# Mergen_Ground_Station_V2_0.net
KiCad netlist of a schematic drawn in EAGLE
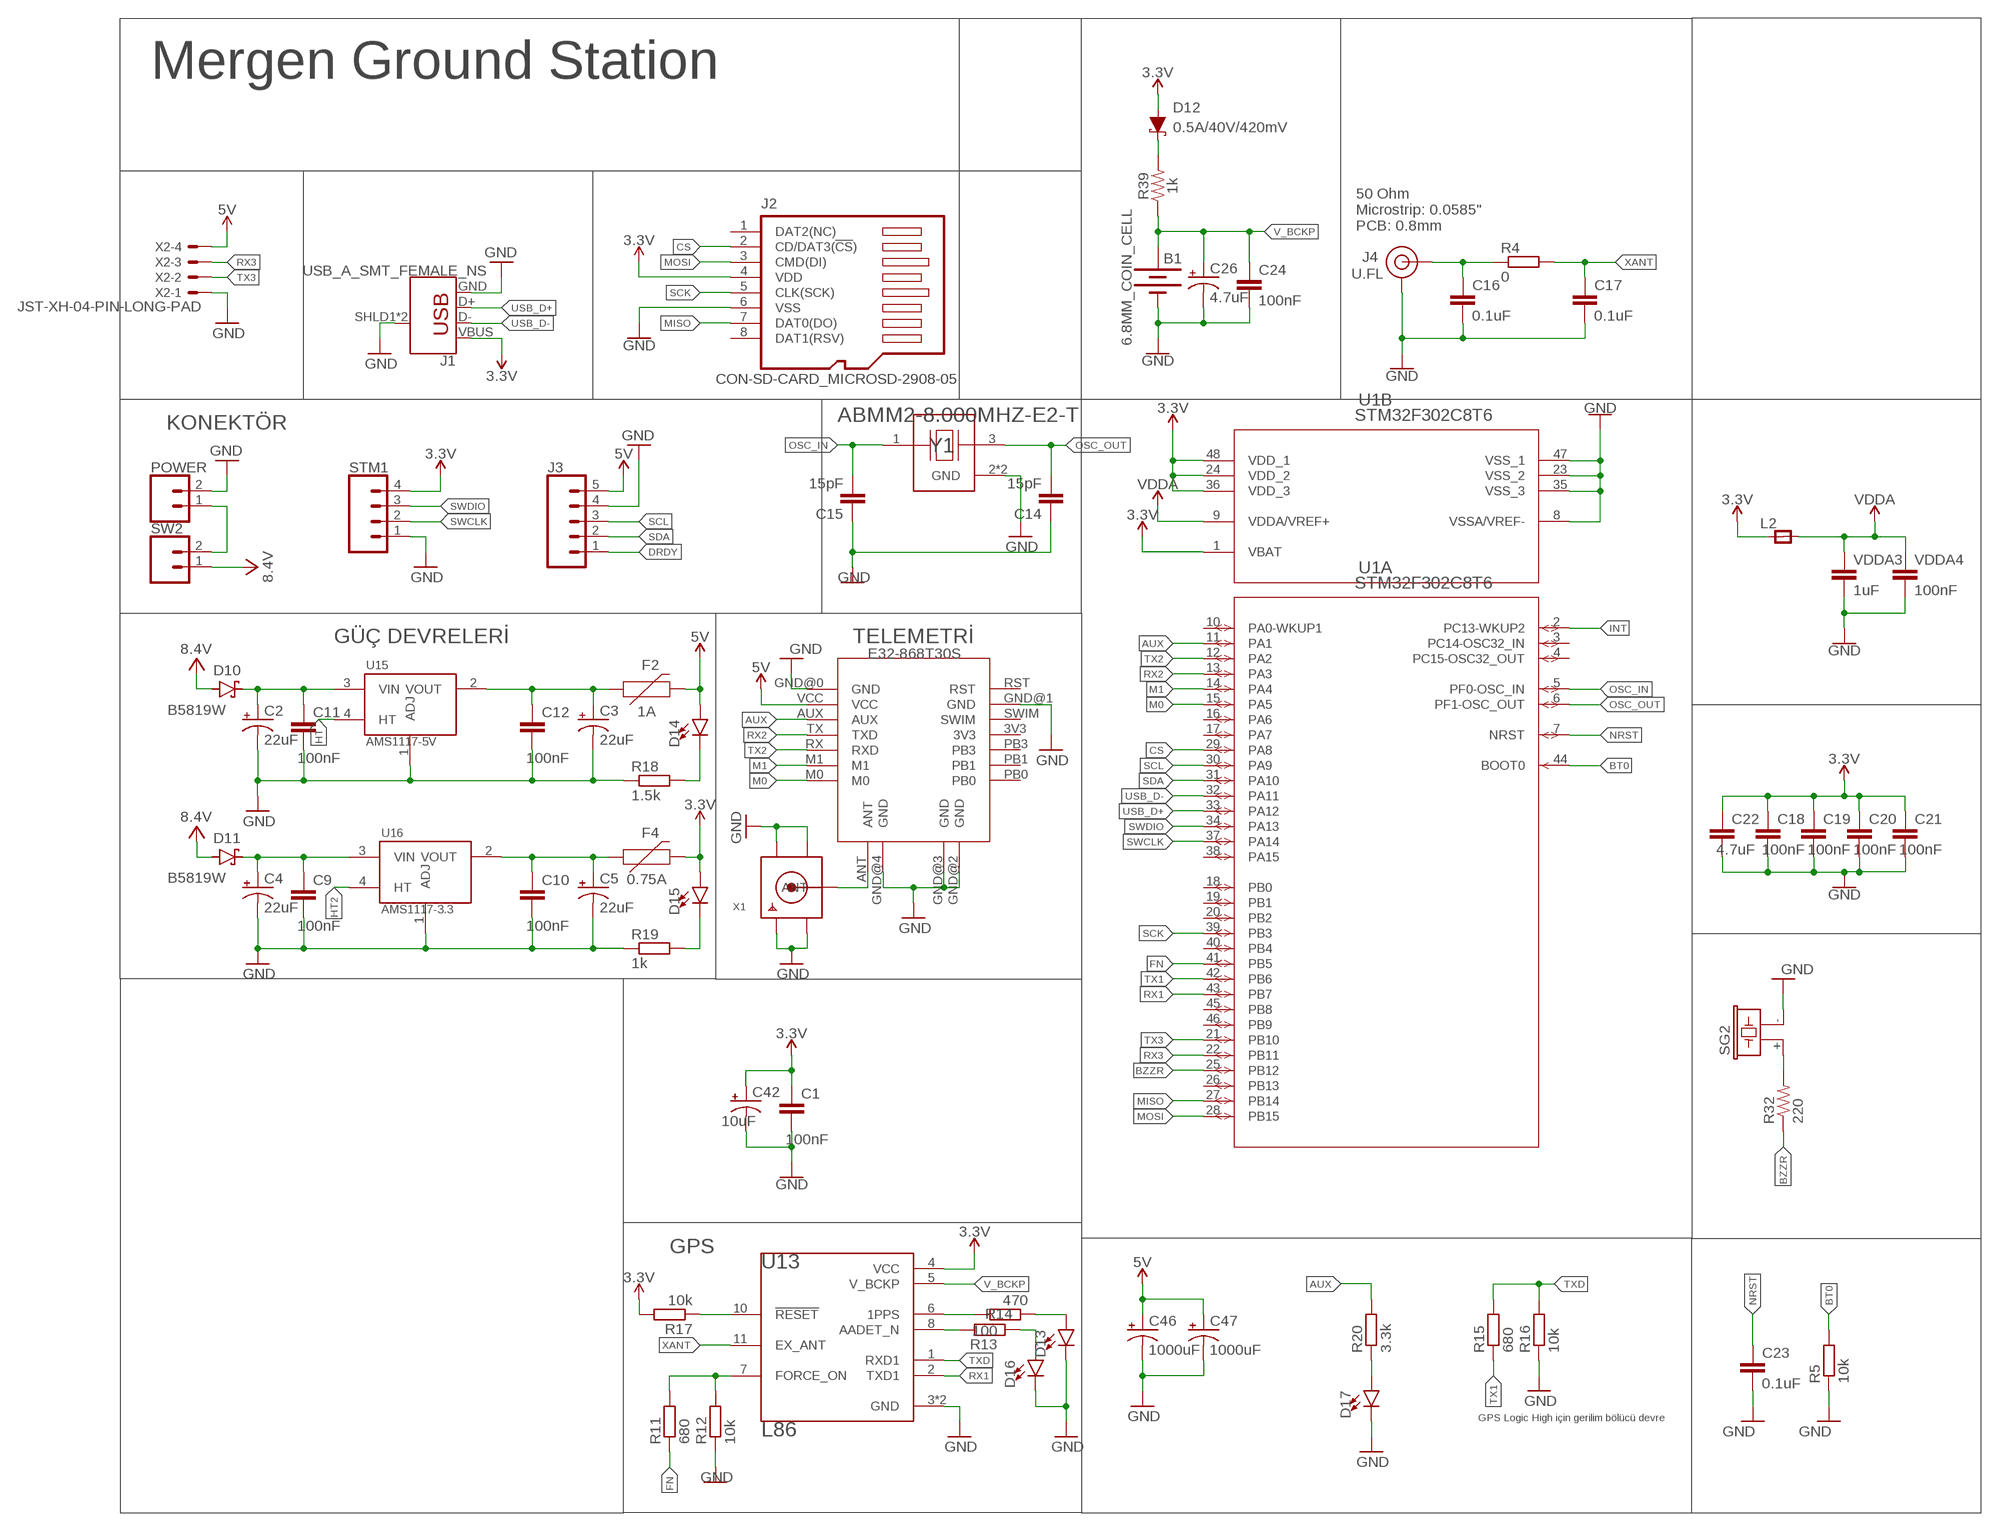
[diagram p0: schematic, sheet 1]

(export (version "E")
  (design (tool "Eeschema 10.0.6"))
  (components
    (comp (ref "B1")
      (value "6.8MM_COIN_CELL")
      (footprint "eagle-import:BATTCON-6.8MM")
      (libsource (lib "eagle-import") (part "BATTERY-6.8MM_SMD"))
    )
    (comp (ref "C1")
      (value "100nF")
      (footprint "eagle-import:C0603")
      (libsource (lib "eagle-import") (part "C-EUC0603"))
    )
    (comp (ref "C2")
      (value "22uF")
      (footprint "eagle-import:CT3528")
      (libsource (lib "eagle-import") (part "rcl_334_CPOL-USCT3528"))
    )
    (comp (ref "C3")
      (value "22uF")
      (footprint "eagle-import:CT3528")
      (libsource (lib "eagle-import") (part "rcl_334_CPOL-USCT3528"))
    )
    (comp (ref "C4")
      (value "22uF")
      (footprint "eagle-import:CT3528")
      (libsource (lib "eagle-import") (part "rcl_334_CPOL-USCT3528"))
    )
    (comp (ref "C5")
      (value "22uF")
      (footprint "eagle-import:CT3528")
      (libsource (lib "eagle-import") (part "rcl_334_CPOL-USCT3528"))
    )
    (comp (ref "C9")
      (value "100nF")
      (footprint "eagle-import:C0603")
      (libsource (lib "eagle-import") (part "C-EUC0603"))
    )
    (comp (ref "C10")
      (value "100nF")
      (footprint "eagle-import:C0603")
      (libsource (lib "eagle-import") (part "C-EUC0603"))
    )
    (comp (ref "C11")
      (value "100nF")
      (footprint "eagle-import:C0603")
      (libsource (lib "eagle-import") (part "C-EUC0603"))
    )
    (comp (ref "C12")
      (value "100nF")
      (footprint "eagle-import:C0603")
      (libsource (lib "eagle-import") (part "C-EUC0603"))
    )
    (comp (ref "C14")
      (value "15pF")
      (footprint "eagle-import:C0603")
      (libsource (lib "eagle-import") (part "C-EUC0603"))
    )
    (comp (ref "C15")
      (value "15pF")
      (footprint "eagle-import:C0603")
      (libsource (lib "eagle-import") (part "C-EUC0603"))
    )
    (comp (ref "C16")
      (value "0.1uF")
      (footprint "eagle-import:C0603")
      (libsource (lib "eagle-import") (part "C-EUC0603"))
    )
    (comp (ref "C17")
      (value "0.1uF")
      (footprint "eagle-import:C0603")
      (libsource (lib "eagle-import") (part "C-EUC0603"))
    )
    (comp (ref "C18")
      (value "100nF")
      (footprint "eagle-import:C0603")
      (libsource (lib "eagle-import") (part "C-EUC0603"))
    )
    (comp (ref "C19")
      (value "100nF")
      (footprint "eagle-import:C0603")
      (libsource (lib "eagle-import") (part "C-EUC0603"))
    )
    (comp (ref "C20")
      (value "100nF")
      (footprint "eagle-import:C0603")
      (libsource (lib "eagle-import") (part "C-EUC0603"))
    )
    (comp (ref "C21")
      (value "100nF")
      (footprint "eagle-import:C0603")
      (libsource (lib "eagle-import") (part "C-EUC0603"))
    )
    (comp (ref "C22")
      (value "4.7uF")
      (footprint "eagle-import:C0603")
      (libsource (lib "eagle-import") (part "C-EUC0603"))
    )
    (comp (ref "C23")
      (value "0.1uF")
      (footprint "eagle-import:C0603")
      (libsource (lib "eagle-import") (part "C-EUC0603"))
    )
    (comp (ref "C24")
      (value "100nF")
      (footprint "eagle-import:C0603")
      (libsource (lib "eagle-import") (part "C-EUC0603"))
    )
    (comp (ref "C26")
      (value "4.7uF")
      (footprint "eagle-import:A_3216-18R")
      (libsource (lib "eagle-import") (part "rcl_334_CPOL-USA/3216-18R"))
    )
    (comp (ref "C42")
      (value "10uF")
      (footprint "eagle-import:EIA3216")
      (libsource (lib "eagle-import") (part "10UF-POLAR-EIA3216-16V-10%(TANT)"))
    )
    (comp (ref "C46")
      (value "1000uF")
      (footprint "eagle-import:150CLZ-1010")
      (libsource (lib "eagle-import") (part "CPOL-US150CLZ-1010"))
    )
    (comp (ref "C47")
      (value "1000uF")
      (footprint "eagle-import:150CLZ-1010")
      (libsource (lib "eagle-import") (part "CPOL-US150CLZ-1010"))
    )
    (comp (ref "D10")
      (value "B5819W")
      (footprint "eagle-import:SODFL3718X115")
      (fields (field (name "MANUFACTURER") "ON Semiconductor") (field (name "MPN") "MBR0520LT1G"))
      (libsource (lib "eagle-import") (part "SCHOTTKY_DO-219MBR0520LT1G"))
    )
    (comp (ref "D11")
      (value "B5819W")
      (footprint "eagle-import:SODFL3718X115")
      (fields (field (name "MANUFACTURER") "ON Semiconductor") (field (name "MPN") "MBR0520LT1G"))
      (libsource (lib "eagle-import") (part "SCHOTTKY_DO-219MBR0520LT1G"))
    )
    (comp (ref "D12")
      (value "0.5A/40V/420mV")
      (footprint "eagle-import:SOD-323")
      (libsource (lib "eagle-import") (part "DIODE-SCHOTTKY-PMEG4005EJ"))
    )
    (comp (ref "D13")
      (value "LED0603")
      (footprint "eagle-import:LED-0603")
      (libsource (lib "eagle-import") (part "LED0603"))
    )
    (comp (ref "D14")
      (value "LED0603")
      (footprint "eagle-import:LED-0603")
      (libsource (lib "eagle-import") (part "LED0603"))
    )
    (comp (ref "D15")
      (value "LED0603")
      (footprint "eagle-import:LED-0603")
      (libsource (lib "eagle-import") (part "LED0603"))
    )
    (comp (ref "D16")
      (value "LED0603")
      (footprint "eagle-import:LED-0603")
      (libsource (lib "eagle-import") (part "LED0603"))
    )
    (comp (ref "D17")
      (value "LED0603")
      (footprint "eagle-import:LED-0603")
      (libsource (lib "eagle-import") (part "LED0603"))
    )
    (comp (ref "F2")
      (value "1A")
      (footprint "eagle-import:1206")
      (libsource (lib "eagle-import") (part "PPTC_HALF-AMP"))
    )
    (comp (ref "F4")
      (value "0.75A")
      (footprint "eagle-import:1206")
      (libsource (lib "eagle-import") (part "PPTC_HALF-AMP"))
    )
    (comp (ref "J1")
      (value "USB_A_SMT_FEMALE_NS")
      (footprint "eagle-import:USB-A-S-NOSILK-FEMALE")
      (libsource (lib "eagle-import") (part "USB_A_SMT_FEMALE_NS"))
    )
    (comp (ref "J2")
      (value "CON-SD-CARD_MICROSD-2908-05")
      (footprint "eagle-import:CON-SD-CARD_2908-05")
      (libsource (lib "eagle-import") (part "CON-SD-CARD_MICROSD-2908-05"))
    )
    (comp (ref "J3")
      (value "CONN_05LOCK_LONGPADS")
      (footprint "eagle-import:1X05_LOCK_LONGPADS")
      (libsource (lib "eagle-import") (part "CONN_05LOCK_LONGPADS"))
    )
    (comp (ref "J4")
      (value "U.FL")
      (footprint "eagle-import:U.FL")
      (libsource (lib "eagle-import") (part "U.FL2PIN"))
    )
    (comp (ref "L2")
      (value "RC-MASTER-SMD_FB_0805MP")
      (footprint "eagle-import:RC-MASTER-SMD_L0805MP")
      (libsource (lib "eagle-import") (part "RC-MASTER-SMD_FB_0805MP"))
    )
    (comp (ref "POWER")
      (value "CONN_023.5MM-NO_SILK")
      (footprint "eagle-import:SCREWTERMINAL-3.5MM-2-NS")
      (libsource (lib "eagle-import") (part "CONN_023.5MM-NO_SILK"))
    )
    (comp (ref "R4")
      (value "0")
      (footprint "eagle-import:R0603")
      (libsource (lib "eagle-import") (part "R-EU_R0603"))
    )
    (comp (ref "R5")
      (value "10k")
      (footprint "eagle-import:R0603")
      (libsource (lib "eagle-import") (part "R-EU_R0603"))
    )
    (comp (ref "R11")
      (value "680")
      (footprint "eagle-import:R0603")
      (libsource (lib "eagle-import") (part "R-EU_R0603"))
    )
    (comp (ref "R12")
      (value "10k")
      (footprint "eagle-import:R0603")
      (libsource (lib "eagle-import") (part "R-EU_R0603"))
    )
    (comp (ref "R13")
      (value "100")
      (footprint "eagle-import:R0603")
      (libsource (lib "eagle-import") (part "R-EU_R0603"))
    )
    (comp (ref "R14")
      (value "470")
      (footprint "eagle-import:R0603")
      (libsource (lib "eagle-import") (part "R-EU_R0603"))
    )
    (comp (ref "R15")
      (value "680")
      (footprint "eagle-import:R0603")
      (libsource (lib "eagle-import") (part "R-EU_R0603"))
    )
    (comp (ref "R16")
      (value "10k")
      (footprint "eagle-import:R0603")
      (libsource (lib "eagle-import") (part "R-EU_R0603"))
    )
    (comp (ref "R17")
      (value "10k")
      (footprint "eagle-import:R0603")
      (libsource (lib "eagle-import") (part "R-EU_R0603"))
    )
    (comp (ref "R18")
      (value "1.5k")
      (footprint "eagle-import:R0603")
      (libsource (lib "eagle-import") (part "R-EU_R0603"))
    )
    (comp (ref "R19")
      (value "1k")
      (footprint "eagle-import:R0603")
      (libsource (lib "eagle-import") (part "R-EU_R0603"))
    )
    (comp (ref "R20")
      (value "3.3k")
      (footprint "eagle-import:R0603")
      (libsource (lib "eagle-import") (part "R-EU_R0603"))
    )
    (comp (ref "R32")
      (value "220")
      (footprint "eagle-import:0603")
      (libsource (lib "eagle-import") (part "0OHM-0603-1/10W-5%"))
    )
    (comp (ref "R39")
      (value "1k")
      (footprint "eagle-import:0603")
      (libsource (lib "eagle-import") (part "1KOHM-0603-1/10W-1%"))
    )
    (comp (ref "SG2")
      (value "F/CM12P")
      (footprint "eagle-import:F_CM12P")
      (libsource (lib "eagle-import") (part "F/CM12P"))
    )
    (comp (ref "STM1")
      (value "CONN_04")
      (footprint "eagle-import:1X04")
      (libsource (lib "eagle-import") (part "CONN_04"))
    )
    (comp (ref "SW2")
      (value "CONN_023.5MM-NO_SILK")
      (footprint "eagle-import:SCREWTERMINAL-3.5MM-2-NS")
      (libsource (lib "eagle-import") (part "CONN_023.5MM-NO_SILK"))
    )
    (comp (ref "U1")
      (value "STM32F302C8T6")
      (footprint "eagle-import:LQFP48-7X7MM")
      (fields (field (name "COPYRIGHT") "Copyright (C) 2018 Accelerated Designs. All rights reserved"))
      (libsource (lib "eagle-import") (part "STM32F302C8T6"))
    )
    (comp (ref "U13")
      (value "L86")
      (footprint "eagle-import:XCVR_L86")
      (fields (field (name "MF") "Quectel"))
      (libsource (lib "eagle-import") (part "L86"))
    )
    (comp (ref "U14")
      (value "E32-868T30S")
      (footprint "eagle-import:E32-868T30S")
      (libsource (lib "eagle-import") (part "E32-868T30S"))
    )
    (comp (ref "U15")
      (value "AMS1117-5V")
      (footprint "eagle-import:SOT229P700X180-4N")
      (fields (field (name "MF") "Advanced Monolithic Systems") (field (name "MP") "AMS1117-3.3"))
      (libsource (lib "eagle-import") (part "AMS1117-3.3"))
    )
    (comp (ref "U16")
      (value "AMS1117-3.3")
      (footprint "eagle-import:SOT229P700X180-4N")
      (fields (field (name "MF") "Advanced Monolithic Systems"))
      (libsource (lib "eagle-import") (part "AMS1117-3.3"))
    )
    (comp (ref "VDDA3")
      (value "1uF")
      (footprint "eagle-import:0603")
      (libsource (lib "eagle-import") (part "0.1UF-0603-25V-(+80/-20%)"))
    )
    (comp (ref "VDDA4")
      (value "100nF")
      (footprint "eagle-import:0603")
      (libsource (lib "eagle-import") (part "0.1UF-0603-25V-(+80/-20%)"))
    )
    (comp (ref "X1")
      (value "SMACONNECTOR")
      (footprint "eagle-import:SMA90_DIP")
      (libsource (lib "eagle-import") (part "SMACONNECTOR"))
    )
    (comp (ref "X2")
      (value "JST-XH-04-PIN-LONG-PAD")
      (footprint "eagle-import:JST-XH-04-PACKAGE-LONG-PAD")
      (libsource (lib "eagle-import") (part "JST-XH-04-PIN-LONG-PAD"))
    )
    (comp (ref "Y1")
      (value "ABMM2-8.000MHZ-E2-T")
      (footprint "eagle-import:XTAL_ABMM2-8.000MHZ-E2-T")
      (fields (field (name "MF") "Abracon"))
      (libsource (lib "eagle-import") (part "ABMM2-8.000MHZ-E2-T"))
    )
  )
  (nets
    (net (code "1") (name "3.3V") (class "Default")
      (node (ref "C1") (pin "1") (pinfunction "1_1") (pintype "passive"))
      (node (ref "C18") (pin "1") (pinfunction "1_1") (pintype "passive"))
      (node (ref "C19") (pin "1") (pinfunction "1_1") (pintype "passive"))
      (node (ref "C20") (pin "1") (pinfunction "1_1") (pintype "passive"))
      (node (ref "C21") (pin "1") (pinfunction "1_1") (pintype "passive"))
      (node (ref "C22") (pin "1") (pinfunction "1_1") (pintype "passive"))
      (node (ref "C42") (pin "+") (pinfunction "+_+") (pintype "passive"))
      (node (ref "D12") (pin "A") (pinfunction "A_A") (pintype "passive"))
      (node (ref "D15") (pin "A") (pinfunction "A_A") (pintype "passive"))
      (node (ref "F4") (pin "2") (pinfunction "2_2") (pintype "bidirectional"))
      (node (ref "J1") (pin "VBUS") (pinfunction "VBUS_VBUS") (pintype "power_in"))
      (node (ref "J2") (pin "4") (pinfunction "VDD_4") (pintype "bidirectional"))
      (node (ref "L2") (pin "1") (pinfunction "1_1") (pintype "passive"))
      (node (ref "R17") (pin "2") (pinfunction "2_2") (pintype "passive"))
      (node (ref "STM1") (pin "4") (pinfunction "4_4") (pintype "passive"))
      (node (ref "U1") (pin "1") (pinfunction "VBAT_1") (pintype "power_in"))
      (node (ref "U1") (pin "24") (pinfunction "VDD_2_24") (pintype "power_in"))
      (node (ref "U1") (pin "36") (pinfunction "VDD_3_36") (pintype "power_in"))
      (node (ref "U1") (pin "48") (pinfunction "VDD_1_48") (pintype "power_in"))
      (node (ref "U13") (pin "4") (pinfunction "VCC_4") (pintype "power_in"))
    )
    (net (code "2") (name "5V") (class "Default")
      (node (ref "C46") (pin "+") (pinfunction "+_+") (pintype "passive"))
      (node (ref "C47") (pin "+") (pinfunction "+_+") (pintype "passive"))
      (node (ref "D14") (pin "A") (pinfunction "A_A") (pintype "passive"))
      (node (ref "F2") (pin "2") (pinfunction "2_2") (pintype "bidirectional"))
      (node (ref "J3") (pin "5") (pinfunction "5_5") (pintype "passive"))
      (node (ref "U14") (pin "VCC") (pinfunction "VCC_VCC") (pintype "bidirectional"))
      (node (ref "X2") (pin "4") (pinfunction "S_4") (pintype "passive"))
    )
    (net (code "3") (name "8.4V") (class "Default")
      (node (ref "D10") (pin "2") (pinfunction "A_2") (pintype "passive"))
      (node (ref "D11") (pin "2") (pinfunction "A_2") (pintype "passive"))
      (node (ref "SW2") (pin "1") (pinfunction "1_1") (pintype "passive"))
    )
    (net (code "4") (name "AUX") (class "Default")
      (node (ref "R20") (pin "2") (pinfunction "2_2") (pintype "passive"))
      (node (ref "U1") (pin "11") (pinfunction "PA1_11") (pintype "bidirectional"))
      (node (ref "U14") (pin "AUX") (pinfunction "AUX_AUX") (pintype "bidirectional"))
    )
    (net (code "5") (name "BT0") (class "Default")
      (node (ref "R5") (pin "2") (pinfunction "2_2") (pintype "passive"))
      (node (ref "U1") (pin "44") (pinfunction "BOOT0_44") (pintype "input"))
    )
    (net (code "6") (name "BZZR") (class "Default")
      (node (ref "R32") (pin "1") (pinfunction "1_1") (pintype "passive"))
      (node (ref "U1") (pin "25") (pinfunction "PB12_25") (pintype "bidirectional"))
    )
    (net (code "7") (name "CS") (class "Default")
      (node (ref "J2") (pin "2") (pinfunction "CD/DAT3(~{CS})_2") (pintype "bidirectional"))
      (node (ref "U1") (pin "29") (pinfunction "PA8_29") (pintype "bidirectional"))
    )
    (net (code "8") (name "DRDY") (class "Default")
      (node (ref "J3") (pin "1") (pinfunction "1_1") (pintype "passive"))
    )
    (net (code "9") (name "FN") (class "Default")
      (node (ref "R11") (pin "1") (pinfunction "1_1") (pintype "passive"))
      (node (ref "U1") (pin "41") (pinfunction "PB5_41") (pintype "bidirectional"))
    )
    (net (code "10") (name "GND") (class "Default")
      (node (ref "B1") (pin "-") (pinfunction "-_-") (pintype "power_in"))
      (node (ref "C1") (pin "2") (pinfunction "2_2") (pintype "passive"))
      (node (ref "C10") (pin "2") (pinfunction "2_2") (pintype "passive"))
      (node (ref "C11") (pin "2") (pinfunction "2_2") (pintype "passive"))
      (node (ref "C12") (pin "2") (pinfunction "2_2") (pintype "passive"))
      (node (ref "C14") (pin "1") (pinfunction "1_1") (pintype "passive"))
      (node (ref "C15") (pin "1") (pinfunction "1_1") (pintype "passive"))
      (node (ref "C16") (pin "2") (pinfunction "2_2") (pintype "passive"))
      (node (ref "C17") (pin "2") (pinfunction "2_2") (pintype "passive"))
      (node (ref "C18") (pin "2") (pinfunction "2_2") (pintype "passive"))
      (node (ref "C19") (pin "2") (pinfunction "2_2") (pintype "passive"))
      (node (ref "C2") (pin "-") (pinfunction "-_-") (pintype "passive"))
      (node (ref "C20") (pin "2") (pinfunction "2_2") (pintype "passive"))
      (node (ref "C21") (pin "2") (pinfunction "2_2") (pintype "passive"))
      (node (ref "C22") (pin "2") (pinfunction "2_2") (pintype "passive"))
      (node (ref "C23") (pin "2") (pinfunction "2_2") (pintype "passive"))
      (node (ref "C24") (pin "2") (pinfunction "2_2") (pintype "passive"))
      (node (ref "C26") (pin "-") (pinfunction "-_-") (pintype "passive"))
      (node (ref "C3") (pin "-") (pinfunction "-_-") (pintype "passive"))
      (node (ref "C4") (pin "-") (pinfunction "-_-") (pintype "passive"))
      (node (ref "C42") (pin "-") (pinfunction "-_-") (pintype "passive"))
      (node (ref "C46") (pin "-") (pinfunction "-_-") (pintype "passive"))
      (node (ref "C47") (pin "-") (pinfunction "-_-") (pintype "passive"))
      (node (ref "C5") (pin "-") (pinfunction "-_-") (pintype "passive"))
      (node (ref "C9") (pin "2") (pinfunction "2_2") (pintype "passive"))
      (node (ref "D13") (pin "C") (pinfunction "C_C") (pintype "passive"))
      (node (ref "D16") (pin "C") (pinfunction "C_C") (pintype "passive"))
      (node (ref "D17") (pin "C") (pinfunction "C_C") (pintype "passive"))
      (node (ref "J1") (pin "GND") (pinfunction "GND_GND") (pintype "power_in"))
      (node (ref "J1") (pin "SHLD1") (pinfunction "SHIELD_SHLD1") (pintype "bidirectional"))
      (node (ref "J1") (pin "SHLD2") (pinfunction "SHIELD_SHLD2") (pintype "bidirectional"))
      (node (ref "J2") (pin "6") (pinfunction "VSS_6") (pintype "bidirectional"))
      (node (ref "J3") (pin "4") (pinfunction "4_4") (pintype "passive"))
      (node (ref "J4") (pin "1") (pinfunction "GND_1") (pintype "bidirectional"))
      (node (ref "J4") (pin "2") (pinfunction "GND_2") (pintype "bidirectional"))
      (node (ref "POWER") (pin "2") (pinfunction "2_2") (pintype "passive"))
      (node (ref "R12") (pin "1") (pinfunction "1_1") (pintype "passive"))
      (node (ref "R16") (pin "1") (pinfunction "1_1") (pintype "passive"))
      (node (ref "R18") (pin "1") (pinfunction "1_1") (pintype "passive"))
      (node (ref "R19") (pin "1") (pinfunction "1_1") (pintype "passive"))
      (node (ref "R5") (pin "1") (pinfunction "1_1") (pintype "passive"))
      (node (ref "SG2") (pin "-") (pinfunction "2_-") (pintype "passive"))
      (node (ref "STM1") (pin "1") (pinfunction "1_1") (pintype "passive"))
      (node (ref "U1") (pin "23") (pinfunction "VSS_2_23") (pintype "power_in"))
      (node (ref "U1") (pin "35") (pinfunction "VSS_3_35") (pintype "power_in"))
      (node (ref "U1") (pin "47") (pinfunction "VSS_1_47") (pintype "power_in"))
      (node (ref "U1") (pin "8") (pinfunction "VSSA/VREF-_8") (pintype "power_in"))
      (node (ref "U13") (pin "12") (pinfunction "GND_12") (pintype "passive"))
      (node (ref "U13") (pin "3") (pinfunction "GND_3") (pintype "passive"))
      (node (ref "U14") (pin "GND@0") (pinfunction "GND_GND@0") (pintype "bidirectional"))
      (node (ref "U14") (pin "GND@1") (pinfunction "GND_GND@1") (pintype "bidirectional"))
      (node (ref "U14") (pin "GND@2") (pinfunction "GND_GND@2") (pintype "bidirectional"))
      (node (ref "U14") (pin "GND@3") (pinfunction "GND_GND@3") (pintype "bidirectional"))
      (node (ref "U14") (pin "GND@4") (pinfunction "GND_GND@4") (pintype "bidirectional"))
      (node (ref "U15") (pin "1") (pinfunction "ADJ_1") (pintype "power_in"))
      (node (ref "U16") (pin "1") (pinfunction "ADJ_1") (pintype "power_in"))
      (node (ref "VDDA3") (pin "2") (pinfunction "2_2") (pintype "passive"))
      (node (ref "VDDA4") (pin "2") (pinfunction "2_2") (pintype "passive"))
      (node (ref "X1") (pin "GND1") (pinfunction "GND1_GND1") (pintype "power_in"))
      (node (ref "X1") (pin "GND2") (pinfunction "GND2_GND2") (pintype "power_in"))
      (node (ref "X1") (pin "GND3") (pinfunction "GND3_GND3") (pintype "power_in"))
      (node (ref "X1") (pin "GND4") (pinfunction "GND4_GND4") (pintype "power_in"))
      (node (ref "X2") (pin "1") (pinfunction "S_1") (pintype "passive"))
      (node (ref "Y1") (pin "2") (pinfunction "GND_2") (pintype "power_in"))
      (node (ref "Y1") (pin "4") (pinfunction "GND_4") (pintype "power_in"))
    )
    (net (code "11") (name "HT") (class "Default")
      (node (ref "U15") (pin "4") (pinfunction "HT_4") (pintype "bidirectional"))
    )
    (net (code "12") (name "HT2") (class "Default")
      (node (ref "U16") (pin "4") (pinfunction "HT_4") (pintype "bidirectional"))
    )
    (net (code "13") (name "INT") (class "Default")
      (node (ref "U1") (pin "2") (pinfunction "PC13-WKUP2_2") (pintype "bidirectional"))
    )
    (net (code "14") (name "M0") (class "Default")
      (node (ref "U1") (pin "15") (pinfunction "PA5_15") (pintype "bidirectional"))
      (node (ref "U14") (pin "M0") (pinfunction "M0_M0") (pintype "bidirectional"))
    )
    (net (code "15") (name "M1") (class "Default")
      (node (ref "U1") (pin "14") (pinfunction "PA4_14") (pintype "bidirectional"))
      (node (ref "U14") (pin "M1") (pinfunction "M1_M1") (pintype "bidirectional"))
    )
    (net (code "16") (name "MISO") (class "Default")
      (node (ref "J2") (pin "7") (pinfunction "DAT0(DO)_7") (pintype "bidirectional"))
      (node (ref "U1") (pin "27") (pinfunction "PB14_27") (pintype "bidirectional"))
    )
    (net (code "17") (name "MOSI") (class "Default")
      (node (ref "J2") (pin "3") (pinfunction "CMD(DI)_3") (pintype "bidirectional"))
      (node (ref "U1") (pin "28") (pinfunction "PB15_28") (pintype "bidirectional"))
    )
    (net (code "18") (name "NRST") (class "Default")
      (node (ref "C23") (pin "1") (pinfunction "1_1") (pintype "passive"))
      (node (ref "U1") (pin "7") (pinfunction "NRST_7") (pintype "bidirectional"))
    )
    (net (code "19") (name "Net-(D10-C)") (class "Default")
      (node (ref "C11") (pin "1") (pinfunction "1_1") (pintype "passive"))
      (node (ref "C2") (pin "+") (pinfunction "+_+") (pintype "passive"))
      (node (ref "D10") (pin "1") (pinfunction "C_1") (pintype "passive"))
      (node (ref "U15") (pin "3") (pinfunction "VIN_3") (pintype "input"))
    )
    (net (code "20") (name "Net-(D11-C)") (class "Default")
      (node (ref "C4") (pin "+") (pinfunction "+_+") (pintype "passive"))
      (node (ref "C9") (pin "1") (pinfunction "1_1") (pintype "passive"))
      (node (ref "D11") (pin "1") (pinfunction "C_1") (pintype "passive"))
      (node (ref "U16") (pin "3") (pinfunction "VIN_3") (pintype "input"))
    )
    (net (code "21") (name "Net-(D12-PadC)") (class "Default")
      (node (ref "D12") (pin "C") (pinfunction "C_C") (pintype "passive"))
      (node (ref "R39") (pin "2") (pinfunction "2_2") (pintype "passive"))
    )
    (net (code "22") (name "Net-(D13-PadA)") (class "Default")
      (node (ref "D13") (pin "A") (pinfunction "A_A") (pintype "passive"))
      (node (ref "R14") (pin "1") (pinfunction "1_1") (pintype "passive"))
    )
    (net (code "23") (name "Net-(D14-PadC)") (class "Default")
      (node (ref "D14") (pin "C") (pinfunction "C_C") (pintype "passive"))
      (node (ref "R18") (pin "2") (pinfunction "2_2") (pintype "passive"))
    )
    (net (code "24") (name "Net-(D15-PadC)") (class "Default")
      (node (ref "D15") (pin "C") (pinfunction "C_C") (pintype "passive"))
      (node (ref "R19") (pin "2") (pinfunction "2_2") (pintype "passive"))
    )
    (net (code "25") (name "Net-(D16-PadA)") (class "Default")
      (node (ref "D16") (pin "A") (pinfunction "A_A") (pintype "passive"))
      (node (ref "R13") (pin "1") (pinfunction "1_1") (pintype "passive"))
    )
    (net (code "26") (name "Net-(D17-PadA)") (class "Default")
      (node (ref "D17") (pin "A") (pinfunction "A_A") (pintype "passive"))
      (node (ref "R20") (pin "1") (pinfunction "1_1") (pintype "passive"))
    )
    (net (code "27") (name "Net-(J4-SIGNAL)") (class "Default")
      (node (ref "C16") (pin "1") (pinfunction "1_1") (pintype "passive"))
      (node (ref "J4") (pin "FEED") (pinfunction "SIGNAL_FEED") (pintype "bidirectional"))
      (node (ref "R4") (pin "1") (pinfunction "1_1") (pintype "passive"))
    )
    (net (code "28") (name "Net-(POWER-Pad1)") (class "Default")
      (node (ref "POWER") (pin "1") (pinfunction "1_1") (pintype "passive"))
      (node (ref "SW2") (pin "2") (pinfunction "2_2") (pintype "passive"))
    )
    (net (code "29") (name "Net-(SG2-1)") (class "Default")
      (node (ref "R32") (pin "2") (pinfunction "2_2") (pintype "passive"))
      (node (ref "SG2") (pin "+") (pinfunction "1_+") (pintype "passive"))
    )
    (net (code "30") (name "Net-(U13-1PPS)") (class "Default")
      (node (ref "R14") (pin "2") (pinfunction "2_2") (pintype "passive"))
      (node (ref "U13") (pin "6") (pinfunction "1PPS_6") (pintype "output"))
    )
    (net (code "31") (name "Net-(U13-AADET_N)") (class "Default")
      (node (ref "R13") (pin "2") (pinfunction "2_2") (pintype "passive"))
      (node (ref "U13") (pin "8") (pinfunction "AADET_N_8") (pintype "output"))
    )
    (net (code "32") (name "Net-(U13-FORCE_ON)") (class "Default")
      (node (ref "R11") (pin "2") (pinfunction "2_2") (pintype "passive"))
      (node (ref "R12") (pin "2") (pinfunction "2_2") (pintype "passive"))
      (node (ref "U13") (pin "7") (pinfunction "FORCE_ON_7") (pintype "input"))
    )
    (net (code "33") (name "Net-(U13-~{RESET})") (class "Default")
      (node (ref "R17") (pin "1") (pinfunction "1_1") (pintype "passive"))
      (node (ref "U13") (pin "10") (pinfunction "~{RESET}_10") (pintype "input"))
    )
    (net (code "34") (name "Net-(U15-VOUT)") (class "Default")
      (node (ref "C12") (pin "1") (pinfunction "1_1") (pintype "passive"))
      (node (ref "C3") (pin "+") (pinfunction "+_+") (pintype "passive"))
      (node (ref "F2") (pin "1") (pinfunction "1_1") (pintype "bidirectional"))
      (node (ref "U15") (pin "2") (pinfunction "VOUT_2") (pintype "output"))
    )
    (net (code "35") (name "Net-(U16-VOUT)") (class "Default")
      (node (ref "C10") (pin "1") (pinfunction "1_1") (pintype "passive"))
      (node (ref "C5") (pin "+") (pinfunction "+_+") (pintype "passive"))
      (node (ref "F4") (pin "1") (pinfunction "1_1") (pintype "bidirectional"))
      (node (ref "U16") (pin "2") (pinfunction "VOUT_2") (pintype "output"))
    )
    (net (code "36") (name "Net-(X1-ANT)") (class "Default")
      (node (ref "U14") (pin "ANT") (pinfunction "ANT_ANT") (pintype "bidirectional"))
      (node (ref "X1") (pin "ANTENNA") (pinfunction "ANT_ANTENNA") (pintype "bidirectional"))
    )
    (net (code "37") (name "OSC_IN") (class "Default")
      (node (ref "C15") (pin "2") (pinfunction "2_2") (pintype "passive"))
      (node (ref "U1") (pin "5") (pinfunction "PF0-OSC_IN_5") (pintype "bidirectional"))
      (node (ref "Y1") (pin "1") (pinfunction "1_1") (pintype "passive"))
    )
    (net (code "38") (name "OSC_OUT") (class "Default")
      (node (ref "C14") (pin "2") (pinfunction "2_2") (pintype "passive"))
      (node (ref "U1") (pin "6") (pinfunction "PF1-OSC_OUT_6") (pintype "bidirectional"))
      (node (ref "Y1") (pin "3") (pinfunction "3_3") (pintype "passive"))
    )
    (net (code "39") (name "RX1") (class "Default")
      (node (ref "U1") (pin "43") (pinfunction "PB7_43") (pintype "bidirectional"))
      (node (ref "U13") (pin "2") (pinfunction "TXD1_2") (pintype "output"))
    )
    (net (code "40") (name "RX2") (class "Default")
      (node (ref "U1") (pin "13") (pinfunction "PA3_13") (pintype "bidirectional"))
      (node (ref "U14") (pin "TX") (pinfunction "TXD_TX") (pintype "bidirectional"))
    )
    (net (code "41") (name "RX3") (class "Default")
      (node (ref "U1") (pin "22") (pinfunction "PB11_22") (pintype "bidirectional"))
      (node (ref "X2") (pin "3") (pinfunction "S_3") (pintype "passive"))
    )
    (net (code "42") (name "SCK") (class "Default")
      (node (ref "J2") (pin "5") (pinfunction "CLK(SCK)_5") (pintype "bidirectional"))
      (node (ref "U1") (pin "39") (pinfunction "PB3_39") (pintype "bidirectional"))
    )
    (net (code "43") (name "SCL") (class "Default")
      (node (ref "J3") (pin "3") (pinfunction "3_3") (pintype "passive"))
      (node (ref "U1") (pin "30") (pinfunction "PA9_30") (pintype "bidirectional"))
    )
    (net (code "44") (name "SDA") (class "Default")
      (node (ref "J3") (pin "2") (pinfunction "2_2") (pintype "passive"))
      (node (ref "U1") (pin "31") (pinfunction "PA10_31") (pintype "bidirectional"))
    )
    (net (code "45") (name "SWCLK") (class "Default")
      (node (ref "STM1") (pin "2") (pinfunction "2_2") (pintype "passive"))
      (node (ref "U1") (pin "37") (pinfunction "PA14_37") (pintype "bidirectional"))
    )
    (net (code "46") (name "SWDIO") (class "Default")
      (node (ref "STM1") (pin "3") (pinfunction "3_3") (pintype "passive"))
      (node (ref "U1") (pin "34") (pinfunction "PA13_34") (pintype "bidirectional"))
    )
    (net (code "47") (name "TX1") (class "Default")
      (node (ref "R15") (pin "1") (pinfunction "1_1") (pintype "passive"))
      (node (ref "U1") (pin "42") (pinfunction "PB6_42") (pintype "bidirectional"))
    )
    (net (code "48") (name "TX2") (class "Default")
      (node (ref "U1") (pin "12") (pinfunction "PA2_12") (pintype "bidirectional"))
      (node (ref "U14") (pin "RX") (pinfunction "RXD_RX") (pintype "bidirectional"))
    )
    (net (code "49") (name "TX3") (class "Default")
      (node (ref "U1") (pin "21") (pinfunction "PB10_21") (pintype "bidirectional"))
      (node (ref "X2") (pin "2") (pinfunction "S_2") (pintype "passive"))
    )
    (net (code "50") (name "TXD") (class "Default")
      (node (ref "R15") (pin "2") (pinfunction "2_2") (pintype "passive"))
      (node (ref "R16") (pin "2") (pinfunction "2_2") (pintype "passive"))
      (node (ref "U13") (pin "1") (pinfunction "RXD1_1") (pintype "input"))
    )
    (net (code "51") (name "USB_D+") (class "Default")
      (node (ref "J1") (pin "D+") (pinfunction "D+_D+") (pintype "bidirectional"))
      (node (ref "U1") (pin "33") (pinfunction "PA12_33") (pintype "bidirectional"))
    )
    (net (code "52") (name "USB_D-") (class "Default")
      (node (ref "J1") (pin "D-") (pinfunction "D-_D-") (pintype "bidirectional"))
      (node (ref "U1") (pin "32") (pinfunction "PA11_32") (pintype "bidirectional"))
    )
    (net (code "53") (name "VDDA") (class "Default")
      (node (ref "L2") (pin "2") (pinfunction "2_2") (pintype "passive"))
      (node (ref "U1") (pin "9") (pinfunction "VDDA/VREF+_9") (pintype "power_in"))
      (node (ref "VDDA3") (pin "1") (pinfunction "1_1") (pintype "passive"))
      (node (ref "VDDA4") (pin "1") (pinfunction "1_1") (pintype "passive"))
    )
    (net (code "54") (name "V_BCKP") (class "Default")
      (node (ref "B1") (pin "+") (pinfunction "+_+") (pintype "power_in"))
      (node (ref "C24") (pin "1") (pinfunction "1_1") (pintype "passive"))
      (node (ref "C26") (pin "+") (pinfunction "+_+") (pintype "passive"))
      (node (ref "R39") (pin "1") (pinfunction "1_1") (pintype "passive"))
      (node (ref "U13") (pin "5") (pinfunction "V_BCKP_5") (pintype "power_in"))
    )
    (net (code "55") (name "XANT") (class "Default")
      (node (ref "C17") (pin "1") (pinfunction "1_1") (pintype "passive"))
      (node (ref "R4") (pin "2") (pinfunction "2_2") (pintype "passive"))
      (node (ref "U13") (pin "11") (pinfunction "EX_ANT_11") (pintype "input"))
    )
    (net (code "56") (name "unconnected-(J2B-DAT1(RSV)-Pad8)") (class "Default")
      (node (ref "J2") (pin "8") (pinfunction "DAT1(RSV)_8") (pintype "bidirectional"))
    )
    (net (code "57") (name "unconnected-(J2B-DAT2(NC)-Pad1)") (class "Default")
      (node (ref "J2") (pin "1") (pinfunction "DAT2(NC)_1") (pintype "bidirectional"))
    )
    (net (code "58") (name "unconnected-(U1A-PA0-WKUP1-Pad10)") (class "Default")
      (node (ref "U1") (pin "10") (pinfunction "PA0-WKUP1_10") (pintype "bidirectional"))
    )
    (net (code "59") (name "unconnected-(U1A-PA6-Pad16)") (class "Default")
      (node (ref "U1") (pin "16") (pinfunction "PA6_16") (pintype "bidirectional"))
    )
    (net (code "60") (name "unconnected-(U1A-PA7-Pad17)") (class "Default")
      (node (ref "U1") (pin "17") (pinfunction "PA7_17") (pintype "bidirectional"))
    )
    (net (code "61") (name "unconnected-(U1A-PA15-Pad38)") (class "Default")
      (node (ref "U1") (pin "38") (pinfunction "PA15_38") (pintype "bidirectional"))
    )
    (net (code "62") (name "unconnected-(U1A-PB0-Pad18)") (class "Default")
      (node (ref "U1") (pin "18") (pinfunction "PB0_18") (pintype "bidirectional"))
    )
    (net (code "63") (name "unconnected-(U1A-PB1-Pad19)") (class "Default")
      (node (ref "U1") (pin "19") (pinfunction "PB1_19") (pintype "bidirectional"))
    )
    (net (code "64") (name "unconnected-(U1A-PB2-Pad20)") (class "Default")
      (node (ref "U1") (pin "20") (pinfunction "PB2_20") (pintype "bidirectional"))
    )
    (net (code "65") (name "unconnected-(U1A-PB4-Pad40)") (class "Default")
      (node (ref "U1") (pin "40") (pinfunction "PB4_40") (pintype "bidirectional"))
    )
    (net (code "66") (name "unconnected-(U1A-PB8-Pad45)") (class "Default")
      (node (ref "U1") (pin "45") (pinfunction "PB8_45") (pintype "bidirectional"))
    )
    (net (code "67") (name "unconnected-(U1A-PB9-Pad46)") (class "Default")
      (node (ref "U1") (pin "46") (pinfunction "PB9_46") (pintype "bidirectional"))
    )
    (net (code "68") (name "unconnected-(U1A-PB13-Pad26)") (class "Default")
      (node (ref "U1") (pin "26") (pinfunction "PB13_26") (pintype "bidirectional"))
    )
    (net (code "69") (name "unconnected-(U1A-PC14-OSC32_IN-Pad3)") (class "Default")
      (node (ref "U1") (pin "3") (pinfunction "PC14-OSC32_IN_3") (pintype "bidirectional"))
    )
    (net (code "70") (name "unconnected-(U1A-PC15-OSC32_OUT-Pad4)") (class "Default")
      (node (ref "U1") (pin "4") (pinfunction "PC15-OSC32_OUT_4") (pintype "bidirectional"))
    )
    (net (code "71") (name "unconnected-(U14-Pad3V3)") (class "Default")
      (node (ref "U14") (pin "3V3") (pinfunction "3V3_3V3") (pintype "bidirectional"))
    )
    (net (code "72") (name "unconnected-(U14-PadPB0)") (class "Default")
      (node (ref "U14") (pin "PB0") (pinfunction "PB0_PB0") (pintype "bidirectional"))
    )
    (net (code "73") (name "unconnected-(U14-PadPB1)") (class "Default")
      (node (ref "U14") (pin "PB1") (pinfunction "PB1_PB1") (pintype "bidirectional"))
    )
    (net (code "74") (name "unconnected-(U14-PadPB3)") (class "Default")
      (node (ref "U14") (pin "PB3") (pinfunction "PB3_PB3") (pintype "bidirectional"))
    )
    (net (code "75") (name "unconnected-(U14-PadRST)") (class "Default")
      (node (ref "U14") (pin "RST") (pinfunction "RST_RST") (pintype "bidirectional"))
    )
    (net (code "76") (name "unconnected-(U14-PadSWIM)") (class "Default")
      (node (ref "U14") (pin "SWIM") (pinfunction "SWIM_SWIM") (pintype "bidirectional"))
    )
  )
)
